# Flags_Register.net
KiCad netlist of a schematic drawn in EasyEDA Pro
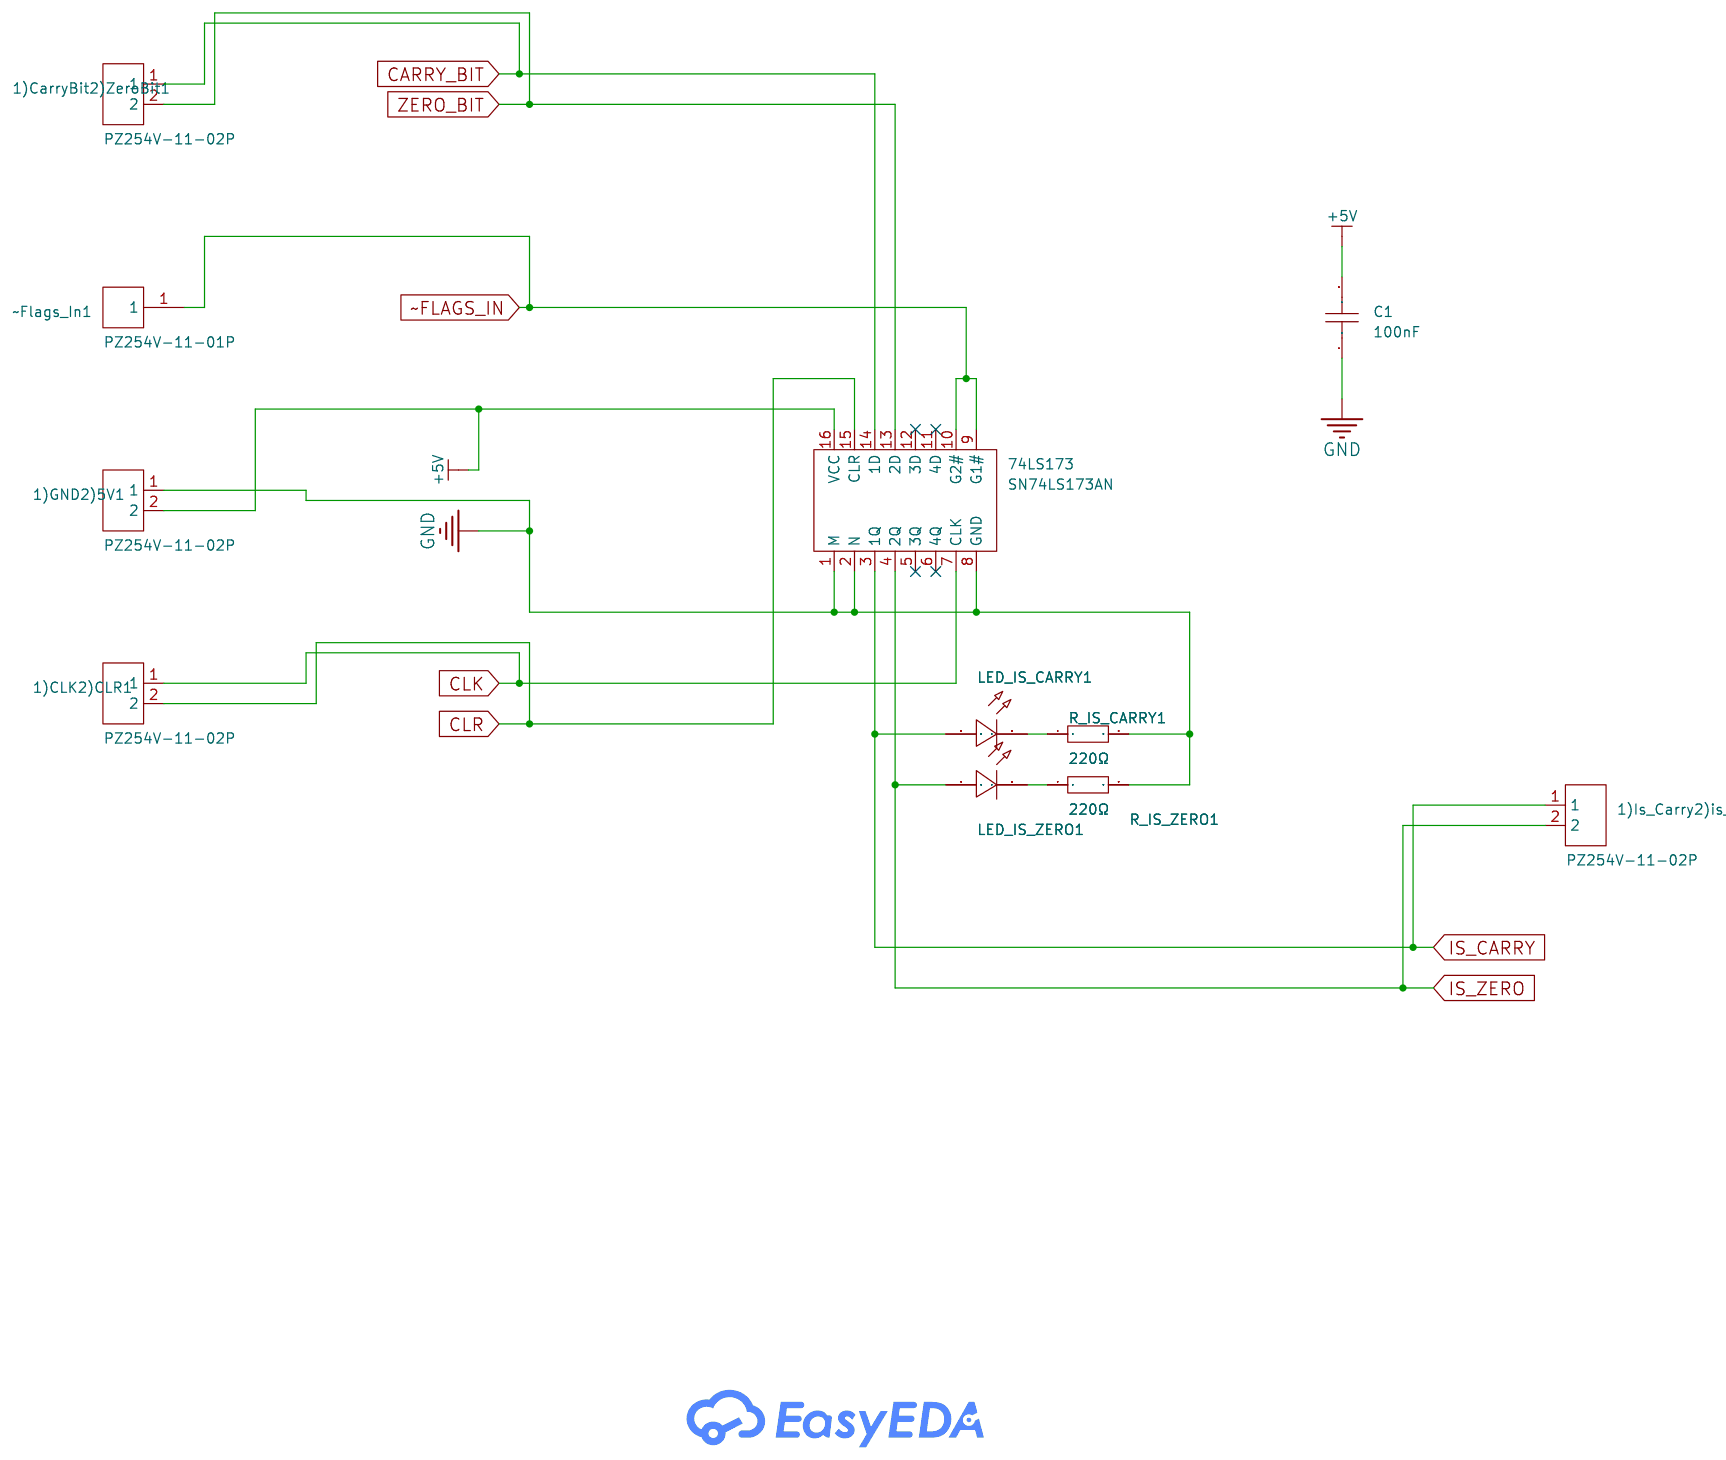
[diagram p0: schematic sheet]

(export (version "E")
  (design (tool "Eeschema 10.0.6"))
  (components
    (comp (ref "1)CarryBit2)ZeroBit1")
      (value "PZ254V-11-02P")
      (footprint "easyedapro:HDR-TH_2P-P2.54-V-M")
      (fields (field (name "Manufacturer") "XFCN(兴飞)"))
      (libsource (lib "easyedapro") (part "PZ254V-11-02P"))
    )
    (comp (ref "1)CLK2)CLR1")
      (value "PZ254V-11-02P")
      (footprint "easyedapro:HDR-TH_2P-P2.54-V-M")
      (fields (field (name "Manufacturer") "XFCN(兴飞)"))
      (libsource (lib "easyedapro") (part "PZ254V-11-02P"))
    )
    (comp (ref "1)GND2)5V1")
      (value "PZ254V-11-02P")
      (footprint "easyedapro:HDR-TH_2P-P2.54-V-M")
      (fields (field (name "Manufacturer") "XFCN(兴飞)"))
      (libsource (lib "easyedapro") (part "PZ254V-11-02P"))
    )
    (comp (ref "1)Is_Carry2)is_Zero1")
      (value "PZ254V-11-02P")
      (footprint "easyedapro:HDR-TH_2P-P2.54-V-M")
      (fields (field (name "Manufacturer") "XFCN(兴飞)"))
      (libsource (lib "easyedapro") (part "PZ254V-11-02P"))
    )
    (comp (ref "74LS173")
      (value "SN74LS173AN")
      (footprint "easyedapro:PDIP-16_L19.3-W6.4-P2.54-LS7.94-BL")
      (fields (field (name "Manufacturer") "TI(德州仪器)"))
      (libsource (lib "easyedapro") (part "SN74LS173AN"))
    )
    (comp (ref "C1")
      (value "100nF")
      (footprint "easyedapro:CAP-TH_L8.5-W5.0-P5.00-D1.2")
      (fields (field (name "Manufacturer Part") "CT4-0805B104K500F3") (field (name "Manufacturer") "FH(风华)"))
      (libsource (lib "easyedapro") (part "CT4-0805B104K500F3"))
    )
    (comp (ref "LED_IS_CARRY1")
      (value "~")
      (footprint "easyedapro:LED-TH_BD5.8-P2.54-FD")
      (libsource (lib "easyedapro") (part "LED_TH-R"))
    )
    (comp (ref "LED_IS_ZERO1")
      (value "~")
      (footprint "easyedapro:LED-TH_BD5.8-P2.54-FD")
      (libsource (lib "easyedapro") (part "LED_TH-R"))
    )
    (comp (ref "R_IS_CARRY1")
      (value "220Ω")
      (footprint "easyedapro:R_AXIAL-0.4")
      (libsource (lib "easyedapro") (part "Res"))
    )
    (comp (ref "R_IS_ZERO1")
      (value "220Ω")
      (footprint "easyedapro:R_AXIAL-0.4")
      (libsource (lib "easyedapro") (part "Res"))
    )
    (comp (ref "~Flags_In1")
      (value "PZ254V-11-01P")
      (footprint "easyedapro:HDR-TH_1P-P2.54-V-M")
      (fields (field (name "Manufacturer") "XFCN(兴飞)"))
      (libsource (lib "easyedapro") (part "PZ254V-11-01P"))
    )
  )
  (nets
    (net (code "1") (name "+5V") (class "Default")
      (node (ref "1)GND2)5V1") (pin "2") (pinfunction "2_2") (pintype "unspecified"))
      (node (ref "74LS173") (pin "16") (pinfunction "VCC_16") (pintype "unspecified"))
      (node (ref "C1") (pin "2") (pinfunction "2_2") (pintype "unspecified"))
    )
    (net (code "2") (name "CARRY_BIT") (class "Default")
      (node (ref "1)CarryBit2)ZeroBit1") (pin "1") (pinfunction "1_1") (pintype "unspecified"))
      (node (ref "74LS173") (pin "14") (pinfunction "1D_14") (pintype "unspecified"))
    )
    (net (code "3") (name "CLK") (class "Default")
      (node (ref "1)CLK2)CLR1") (pin "1") (pinfunction "1_1") (pintype "unspecified"))
      (node (ref "74LS173") (pin "7") (pinfunction "CLK_7") (pintype "unspecified"))
    )
    (net (code "4") (name "CLR") (class "Default")
      (node (ref "1)CLK2)CLR1") (pin "2") (pinfunction "2_2") (pintype "unspecified"))
      (node (ref "74LS173") (pin "15") (pinfunction "CLR_15") (pintype "unspecified"))
    )
    (net (code "5") (name "GND") (class "Default")
      (node (ref "1)GND2)5V1") (pin "1") (pinfunction "1_1") (pintype "unspecified"))
      (node (ref "74LS173") (pin "1") (pinfunction "M_1") (pintype "unspecified"))
      (node (ref "74LS173") (pin "2") (pinfunction "N_2") (pintype "unspecified"))
      (node (ref "74LS173") (pin "8") (pinfunction "GND_8") (pintype "unspecified"))
      (node (ref "C1") (pin "1") (pinfunction "1_1") (pintype "unspecified"))
      (node (ref "R_IS_CARRY1") (pin "2") (pinfunction "2_2") (pintype "input"))
      (node (ref "R_IS_ZERO1") (pin "2") (pinfunction "2_2") (pintype "input"))
    )
    (net (code "6") (name "IS_CARRY") (class "Default")
      (node (ref "1)Is_Carry2)is_Zero1") (pin "1") (pinfunction "1_1") (pintype "unspecified"))
      (node (ref "74LS173") (pin "3") (pinfunction "1Q_3") (pintype "unspecified"))
      (node (ref "LED_IS_CARRY1") (pin "1") (pinfunction "C_1") (pintype "input"))
    )
    (net (code "7") (name "IS_ZERO") (class "Default")
      (node (ref "1)Is_Carry2)is_Zero1") (pin "2") (pinfunction "2_2") (pintype "unspecified"))
      (node (ref "74LS173") (pin "4") (pinfunction "2Q_4") (pintype "unspecified"))
      (node (ref "LED_IS_ZERO1") (pin "1") (pinfunction "C_1") (pintype "input"))
    )
    (net (code "8") (name "Net-(LED_IS_CARRY1-A)") (class "Default")
      (node (ref "LED_IS_CARRY1") (pin "2") (pinfunction "A_2") (pintype "input"))
      (node (ref "R_IS_CARRY1") (pin "1") (pinfunction "1_1") (pintype "input"))
    )
    (net (code "9") (name "Net-(LED_IS_ZERO1-A)") (class "Default")
      (node (ref "LED_IS_ZERO1") (pin "2") (pinfunction "A_2") (pintype "input"))
      (node (ref "R_IS_ZERO1") (pin "1") (pinfunction "1_1") (pintype "input"))
    )
    (net (code "10") (name "ZERO_BIT") (class "Default")
      (node (ref "1)CarryBit2)ZeroBit1") (pin "2") (pinfunction "2_2") (pintype "unspecified"))
      (node (ref "74LS173") (pin "13") (pinfunction "2D_13") (pintype "unspecified"))
    )
    (net (code "11") (name "unconnected-(74LS173-3D-Pad12)") (class "Default")
      (node (ref "74LS173") (pin "12") (pinfunction "3D_12") (pintype "unspecified+no_connect"))
    )
    (net (code "12") (name "unconnected-(74LS173-3Q-Pad5)") (class "Default")
      (node (ref "74LS173") (pin "5") (pinfunction "3Q_5") (pintype "unspecified+no_connect"))
    )
    (net (code "13") (name "unconnected-(74LS173-4D-Pad11)") (class "Default")
      (node (ref "74LS173") (pin "11") (pinfunction "4D_11") (pintype "unspecified+no_connect"))
    )
    (net (code "14") (name "unconnected-(74LS173-4Q-Pad6)") (class "Default")
      (node (ref "74LS173") (pin "6") (pinfunction "4Q_6") (pintype "unspecified+no_connect"))
    )
    (net (code "15") (name "~FLAGS_IN") (class "Default")
      (node (ref "74LS173") (pin "10") (pinfunction "G2#_10") (pintype "unspecified"))
      (node (ref "74LS173") (pin "9") (pinfunction "G1#_9") (pintype "unspecified"))
      (node (ref "~Flags_In1") (pin "1") (pinfunction "1_1") (pintype "unspecified"))
    )
  )
)
